# power.net
KiCad netlist of a schematic drawn in Altium Designer
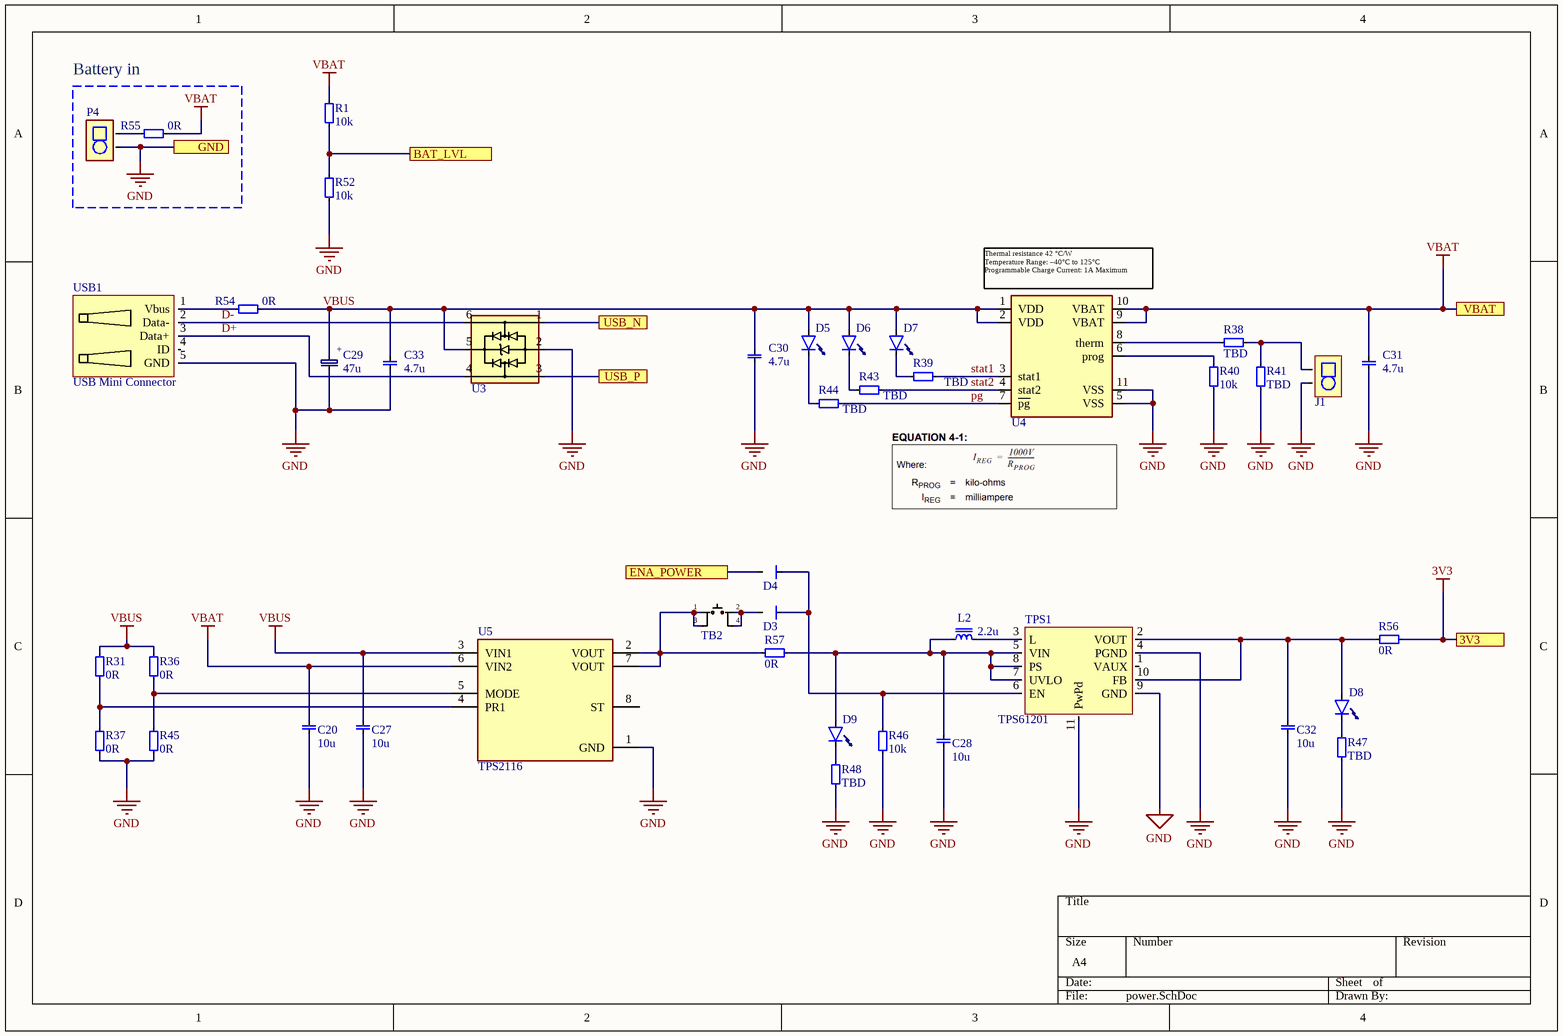
[diagram p0: power.SchDoc]

(export (version "E")
  (design (tool "Eeschema 10.0.6"))
  (components
    (comp (ref "C20")
      (value "10u")
      (footprint "0402 CAP")
      (fields
        (field (name "MANUFACTURER PART NO") "GRM155R61A106ME11D")
        (field (name "Comment") "0402 capacitor")
      )
      (libsource (lib "jclib") (part "0402 capacitor"))
    )
    (comp (ref "C27")
      (value "10u")
      (footprint "0402 CAP")
      (fields
        (field (name "MANUFACTURER PART NO") "GRM155R61A106ME11D")
        (field (name "Comment") "0402 capacitor")
      )
      (libsource (lib "jclib") (part "0402 capacitor"))
    )
    (comp (ref "C28")
      (value "10u")
      (footprint "0402 CAP")
      (fields
        (field (name "MANUFACTURER PART NO") "GRM155R61A106ME11D")
        (field (name "Comment") "0402 capacitor")
      )
      (libsource (lib "jclib") (part "0402 capacitor"))
    )
    (comp (ref "C29")
      (value "47u")
      (footprint "CASE_B")
      (fields (field (name "MANUFACTURER PART NO") "TAJB476M010RNJ") (field (name "Comment") "Cap, case B"))
      (libsource (lib "jclib") (part "Cap, case B"))
    )
    (comp (ref "C30")
      (value "4.7u")
      (footprint "0603 cap")
      (fields
        (field (name "MANUFACTURER PART NO") "GRM188C81C475KE11D")
        (field (name "Comment") "0603, capacitor")
      )
      (libsource (lib "jclib") (part "0603, capacitor"))
    )
    (comp (ref "C31")
      (value "4.7u")
      (footprint "0603 cap")
      (fields
        (field (name "MANUFACTURER PART NO") "GRM188C81C475KE11D")
        (field (name "Comment") "0603, capacitor")
      )
      (libsource (lib "jclib") (part "0603, capacitor"))
    )
    (comp (ref "C32")
      (value "10u")
      (footprint "0402 CAP")
      (fields
        (field (name "MANUFACTURER PART NO") "GRM155R61A106ME11D")
        (field (name "Comment") "0402 capacitor")
      )
      (libsource (lib "jclib") (part "0402 capacitor"))
    )
    (comp (ref "C33")
      (value "4.7u")
      (footprint "0603 cap")
      (fields
        (field (name "MANUFACTURER PART NO") "GRM188C81C475KE11D")
        (field (name "Comment") "0603, capacitor")
      )
      (libsource (lib "jclib") (part "0603, capacitor"))
    )
    (comp (ref "D3")
      (value "Diode, SMD")
      (footprint "SOD323")
      (fields (field (name "MANUFACTURER PART NO") "CUS05S30H3FCT-ND"))
      (libsource (lib "jclib") (part "Diode, SMD"))
    )
    (comp (ref "D4")
      (value "Diode, SMD")
      (footprint "SOD323")
      (fields (field (name "MANUFACTURER PART NO") "CUS05S30H3FCT-ND"))
      (libsource (lib "jclib") (part "Diode, SMD"))
    )
    (comp (ref "D5")
      (value "0603, LED")
      (footprint "0603 LED")
      (fields (field (name "MANUFACTURER PART NO") "5988081107F"))
      (libsource (lib "jclib") (part "0603, LED"))
    )
    (comp (ref "D6")
      (value "0603, LED")
      (footprint "0603 LED")
      (fields (field (name "MANUFACTURER PART NO") "150060SS75003"))
      (libsource (lib "jclib") (part "0603, LED"))
    )
    (comp (ref "D7")
      (value "0603, LED")
      (footprint "0603 LED")
      (fields (field (name "MANUFACTURER PART NO") "150060SS75003"))
      (libsource (lib "jclib") (part "0603, LED"))
    )
    (comp (ref "D8")
      (value "0603, LED")
      (footprint "0603 LED")
      (fields (field (name "MANUFACTURER PART NO") "5988081107F"))
      (libsource (lib "jclib") (part "0603, LED"))
    )
    (comp (ref "D9")
      (value "0603, LED")
      (footprint "0603 LED")
      (fields (field (name "MANUFACTURER PART NO") "5988081107F"))
      (libsource (lib "jclib") (part "0603, LED"))
    )
    (comp (ref "J1")
      (value "Molex 0530480210")
      (footprint "MOLEX_0530480210")
      (description "PicoBlade Header R/A, 1.25 mm,")
      (fields (field (name "MANUFACTURER PART NO") "0530480210"))
      (libsource (lib "jclib") (part "Molex 0530480210"))
    )
    (comp (ref "L2")
      (value "2.2u")
      (footprint "SRR4028")
      (description "2,2µH, 2.0 A, 28 mOhm")
      (fields (field (name "MANUFACTURER PART NO") "SRR4028-2R2Y") (field (name "Comment") "Coil, SRR4028"))
      (libsource (lib "jclib") (part "Coil, SRR4028"))
    )
    (comp (ref "P4")
      (value "JST Connector")
      (footprint "JST_S2B-PH-K-S(LF)(SN)")
      (description "Connector Header Through Hole, Right Angle 2 position")
      (fields (field (name "MANUFACTURER PART NO") "S2B-PH-K-S"))
      (libsource (lib "jclib") (part "JST Connector"))
    )
    (comp (ref "R1")
      (value "10k")
      (footprint "0402 res")
      (description "311-10.0KLRCT-ND")
      (fields (field (name "Comment") "0603, resistor"))
      (libsource (lib "jclib") (part "0603, resistor"))
    )
    (comp (ref "R31")
      (value "0R")
      (footprint "0402 res")
      (fields
        (field (name "MANUFACTURER PART NO") "RMCF0402ZT0R00")
        (field (name "Comment") "0603, resistor")
      )
      (libsource (lib "jclib") (part "0603, resistor"))
    )
    (comp (ref "R36")
      (value "0R")
      (footprint "0402 res")
      (fields
        (field (name "MANUFACTURER PART NO") "RMCF0402ZT0R00")
        (field (name "Comment") "0603, resistor")
      )
      (libsource (lib "jclib") (part "0603, resistor"))
    )
    (comp (ref "R37")
      (value "0R")
      (footprint "0402 res")
      (fields
        (field (name "MANUFACTURER PART NO") "RMCF0402ZT0R00")
        (field (name "Comment") "0603, resistor")
      )
      (libsource (lib "jclib") (part "0603, resistor"))
    )
    (comp (ref "R38")
      (value "TBD")
      (footprint "0402 res")
      (fields (field (name "Comment") "0603, resistor"))
      (libsource (lib "jclib") (part "0603, resistor"))
    )
    (comp (ref "R39")
      (value "TBD")
      (footprint "0402 res")
      (fields (field (name "Comment") "0603, resistor"))
      (libsource (lib "jclib") (part "0603, resistor"))
    )
    (comp (ref "R40")
      (value "10k")
      (footprint "0402 res")
      (fields
        (field (name "MANUFACTURER PART NO") "311-10.0KLRCT-ND")
        (field (name "Comment") "0603, resistor")
      )
      (libsource (lib "jclib") (part "0603, resistor"))
    )
    (comp (ref "R41")
      (value "TBD")
      (footprint "0402 res")
      (fields (field (name "Comment") "0603, resistor"))
      (libsource (lib "jclib") (part "0603, resistor"))
    )
    (comp (ref "R43")
      (value "TBD")
      (footprint "0402 res")
      (fields (field (name "Comment") "0603, resistor"))
      (libsource (lib "jclib") (part "0603, resistor"))
    )
    (comp (ref "R44")
      (value "TBD")
      (footprint "0402 res")
      (fields (field (name "Comment") "0603, resistor"))
      (libsource (lib "jclib") (part "0603, resistor"))
    )
    (comp (ref "R45")
      (value "0R")
      (footprint "0402 res")
      (fields
        (field (name "MANUFACTURER PART NO") "RMCF0402ZT0R00")
        (field (name "Comment") "0603, resistor")
      )
      (libsource (lib "jclib") (part "0603, resistor"))
    )
    (comp (ref "R46")
      (value "10k")
      (footprint "0402 res")
      (fields
        (field (name "MANUFACTURER PART NO") "311-10.0KLRCT-ND")
        (field (name "Comment") "0603, resistor")
      )
      (libsource (lib "jclib") (part "0603, resistor"))
    )
    (comp (ref "R47")
      (value "TBD")
      (footprint "0402 res")
      (fields (field (name "Comment") "0603, resistor"))
      (libsource (lib "jclib") (part "0603, resistor"))
    )
    (comp (ref "R48")
      (value "TBD")
      (footprint "0402 res")
      (fields (field (name "Comment") "0603, resistor"))
      (libsource (lib "jclib") (part "0603, resistor"))
    )
    (comp (ref "R52")
      (value "10k")
      (footprint "0402 res")
      (description "311-10.0KLRCT-ND")
      (fields (field (name "Comment") "0603, resistor"))
      (libsource (lib "jclib") (part "0603, resistor"))
    )
    (comp (ref "R54")
      (value "0R")
      (footprint "0603")
      (fields (field (name "MANUFACTURER PART NO") "541-0.0GCT-ND") (field (name "Comment") "0603, resistor"))
      (libsource (lib "jclib") (part "0603, resistor"))
    )
    (comp (ref "R55")
      (value "0R")
      (footprint "0603")
      (fields (field (name "MANUFACTURER PART NO") "541-0.0GCT-ND") (field (name "Comment") "0603, resistor"))
      (libsource (lib "jclib") (part "0603, resistor"))
    )
    (comp (ref "R56")
      (value "0R")
      (footprint "0603")
      (fields (field (name "MANUFACTURER PART NO") "541-0.0GCT-ND") (field (name "Comment") "0603, resistor"))
      (libsource (lib "jclib") (part "0603, resistor"))
    )
    (comp (ref "R57")
      (value "0R")
      (footprint "0603")
      (fields (field (name "MANUFACTURER PART NO") "541-0.0GCT-ND") (field (name "Comment") "0603, resistor"))
      (libsource (lib "jclib") (part "0603, resistor"))
    )
    (comp (ref "TB2")
      (value "Tactile Button")
      (footprint "tacButton smd")
      (description "Tactile Switch Small Low")
      (fields (field (name "MANUFACTURER PART NO") "430182043816"))
      (libsource (lib "jclib") (part "TacButton SMD"))
    )
    (comp (ref "TPS1")
      (value "TPS61201")
      (footprint "PSON10N")
      (description "TPS6120x Low Input Voltage Synchronous Boost Converter")
      (fields (field (name "MANUFACTURER PART NO") "TPS61201DRCR"))
      (libsource (lib "jclib") (part "TPS6120x"))
    )
    (comp (ref "U3")
      (value "USBLC6-2")
      (footprint "SOT236")
      (description "Very low capacitance 2 data-line and VBUS ESD protection")
      (fields (field (name "MANUFACTURER PART NO") "USBLC6-2SC6"))
      (libsource (lib "jclib") (part "USBLC6-2"))
    )
    (comp (ref "U4")
      (value "MCP73833/4")
      (footprint "DFN10")
      (description "Stand-Alone Linear Li-Ion / Li-Polymer Charge\r\nManagement Controller")
      (fields (field (name "MANUFACTURER PART NO") "MCP73833-NVI/MF"))
      (libsource (lib "jclib") (part "MCP73833/4"))
    )
    (comp (ref "U5")
      (value "TPS2116")
      (footprint "SOTFL50P160X60-8N")
      (description "1.6 V to 5.5 V, 2.5-A Low IQ Power Mux with Manual and Priority Switchover")
      (fields (field (name "MANUFACTURER PART NO") "TPS2116DRLR"))
      (libsource (lib "urad") (part "TPS2116"))
    )
    (comp (ref "USB1")
      (value "USB Mini Connector")
      (footprint "USB Mini TH")
      (fields (field (name "MANUFACTURER PART NO") "XM7D-0512"))
      (libsource (lib "jclib") (part "USB Mini Connector"))
    )
  )
  (nets
    (net (code "1") (name "/BAT_LVL") (class "Default")
      (node (ref "R1") (pin "1") (pinfunction "1_1") (pintype "passive"))
      (node (ref "R52") (pin "0") (pinfunction "0_0") (pintype "passive"))
    )
    (net (code "2") (name "/D+") (class "Default")
      (node (ref "U3") (pin "4") (pinfunction "4_4") (pintype "passive"))
      (node (ref "USB1") (pin "3") (pinfunction "Data+_3") (pintype "passive"))
    )
    (net (code "3") (name "/D-") (class "Default")
      (node (ref "U3") (pin "6") (pinfunction "6_6") (pintype "passive"))
      (node (ref "USB1") (pin "2") (pinfunction "Data-_2") (pintype "passive"))
    )
    (net (code "4") (name "/ENA_POWER") (class "Default")
      (node (ref "D4") (pin "2") (pinfunction "2_2") (pintype "passive"))
    )
    (net (code "5") (name "/USB_N") (class "Default")
      (node (ref "U3") (pin "1") (pinfunction "1_1") (pintype "passive"))
    )
    (net (code "6") (name "/USB_P") (class "Default")
      (node (ref "U3") (pin "3") (pinfunction "3_3") (pintype "passive"))
    )
    (net (code "7") (name "/stat1") (class "Default")
      (node (ref "R39") (pin "1") (pinfunction "1_1") (pintype "passive"))
      (node (ref "U4") (pin "3") (pinfunction "stat1_3") (pintype "passive"))
    )
    (net (code "8") (name "/stat2") (class "Default")
      (node (ref "R43") (pin "1") (pinfunction "1_1") (pintype "passive"))
      (node (ref "U4") (pin "4") (pinfunction "stat2_4") (pintype "passive"))
    )
    (net (code "9") (name "/~{pg}") (class "Default")
      (node (ref "R44") (pin "1") (pinfunction "1_1") (pintype "passive"))
      (node (ref "U4") (pin "7") (pinfunction "~{pg}_7") (pintype "passive"))
    )
    (net (code "10") (name "3V3") (class "Default")
      (node (ref "R56") (pin "0") (pinfunction "0_0") (pintype "passive"))
    )
    (net (code "11") (name "GND") (class "Default")
      (node (ref "C20") (pin "0") (pinfunction "0_0") (pintype "passive"))
      (node (ref "C27") (pin "0") (pinfunction "0_0") (pintype "passive"))
      (node (ref "C28") (pin "0") (pinfunction "0_0") (pintype "passive"))
      (node (ref "C29") (pin "1") (pinfunction "1_1") (pintype "passive"))
      (node (ref "C30") (pin "0") (pinfunction "0_0") (pintype "passive"))
      (node (ref "C31") (pin "0") (pinfunction "0_0") (pintype "passive"))
      (node (ref "C32") (pin "0") (pinfunction "0_0") (pintype "passive"))
      (node (ref "C33") (pin "0") (pinfunction "0_0") (pintype "passive"))
      (node (ref "J1") (pin "2") (pinfunction "2_2") (pintype "passive"))
      (node (ref "P4") (pin "2") (pinfunction "2_2") (pintype "passive"))
      (node (ref "R37") (pin "0") (pinfunction "0_0") (pintype "passive"))
      (node (ref "R40") (pin "0") (pinfunction "0_0") (pintype "passive"))
      (node (ref "R41") (pin "0") (pinfunction "0_0") (pintype "passive"))
      (node (ref "R45") (pin "0") (pinfunction "0_0") (pintype "passive"))
      (node (ref "R46") (pin "0") (pinfunction "0_0") (pintype "passive"))
      (node (ref "R47") (pin "1") (pinfunction "1_1") (pintype "passive"))
      (node (ref "R48") (pin "1") (pinfunction "1_1") (pintype "passive"))
      (node (ref "R52") (pin "1") (pinfunction "1_1") (pintype "passive"))
      (node (ref "TPS1") (pin "11") (pinfunction "PwPd_11") (pintype "passive"))
      (node (ref "TPS1") (pin "4") (pinfunction "PGND_4") (pintype "passive"))
      (node (ref "TPS1") (pin "9") (pinfunction "GND_9") (pintype "passive"))
      (node (ref "U3") (pin "2") (pinfunction "2_2") (pintype "passive"))
      (node (ref "U4") (pin "11") (pinfunction "VSS_11") (pintype "passive"))
      (node (ref "U4") (pin "5") (pinfunction "VSS_5") (pintype "passive"))
      (node (ref "U5") (pin "1") (pinfunction "GND_1") (pintype "passive"))
      (node (ref "USB1") (pin "5") (pinfunction "GND_5") (pintype "passive"))
    )
    (net (code "12") (name "Net-(D3-Pad2)") (class "Default")
      (node (ref "D3") (pin "2") (pinfunction "2_2") (pintype "passive"))
      (node (ref "TB2") (pin "2") (pinfunction "2_2") (pintype "passive"))
      (node (ref "TB2") (pin "4") (pinfunction "4_4") (pintype "passive"))
    )
    (net (code "13") (name "Net-(D5-Cathode)") (class "Default")
      (node (ref "D5") (pin "0") (pinfunction "Cathode_0") (pintype "passive"))
      (node (ref "R44") (pin "0") (pinfunction "0_0") (pintype "passive"))
    )
    (net (code "14") (name "Net-(D6-Cathode)") (class "Default")
      (node (ref "D6") (pin "0") (pinfunction "Cathode_0") (pintype "passive"))
      (node (ref "R43") (pin "0") (pinfunction "0_0") (pintype "passive"))
    )
    (net (code "15") (name "Net-(D7-Cathode)") (class "Default")
      (node (ref "D7") (pin "0") (pinfunction "Cathode_0") (pintype "passive"))
      (node (ref "R39") (pin "0") (pinfunction "0_0") (pintype "passive"))
    )
    (net (code "16") (name "Net-(D8-Cathode)") (class "Default")
      (node (ref "D8") (pin "0") (pinfunction "Cathode_0") (pintype "passive"))
      (node (ref "R47") (pin "0") (pinfunction "0_0") (pintype "passive"))
    )
    (net (code "17") (name "Net-(D9-Cathode)") (class "Default")
      (node (ref "D9") (pin "0") (pinfunction "Cathode_0") (pintype "passive"))
      (node (ref "R48") (pin "0") (pinfunction "0_0") (pintype "passive"))
    )
    (net (code "18") (name "Net-(J1-Pad1)") (class "Default")
      (node (ref "J1") (pin "1") (pinfunction "1_1") (pintype "passive"))
      (node (ref "R38") (pin "0") (pinfunction "0_0") (pintype "passive"))
      (node (ref "R41") (pin "1") (pinfunction "1_1") (pintype "passive"))
    )
    (net (code "19") (name "Net-(P4-Pad1)") (class "Default")
      (node (ref "P4") (pin "1") (pinfunction "1_1") (pintype "passive"))
      (node (ref "R55") (pin "1") (pinfunction "1_1") (pintype "passive"))
    )
    (net (code "20") (name "Net-(R57-Pad1)") (class "Default")
      (node (ref "R57") (pin "1") (pinfunction "1_1") (pintype "passive"))
      (node (ref "TB2") (pin "1") (pinfunction "1_1") (pintype "passive"))
      (node (ref "TB2") (pin "3") (pinfunction "3_3") (pintype "passive"))
      (node (ref "U5") (pin "2") (pinfunction "VOUT_2") (pintype "passive"))
      (node (ref "U5") (pin "7") (pinfunction "VOUT_7") (pintype "passive"))
    )
    (net (code "21") (name "Net-(TPS1-EN)") (class "Default")
      (node (ref "D3") (pin "1") (pinfunction "1_1") (pintype "passive"))
      (node (ref "D4") (pin "1") (pinfunction "1_1") (pintype "passive"))
      (node (ref "R46") (pin "1") (pinfunction "1_1") (pintype "passive"))
      (node (ref "TPS1") (pin "6") (pinfunction "EN_6") (pintype "passive"))
    )
    (net (code "22") (name "Net-(TPS1-FB)") (class "Default")
      (node (ref "C32") (pin "1") (pinfunction "1_1") (pintype "passive"))
      (node (ref "D8") (pin "1") (pinfunction "1_1") (pintype "passive"))
      (node (ref "R56") (pin "1") (pinfunction "1_1") (pintype "passive"))
      (node (ref "TPS1") (pin "10") (pinfunction "FB_10") (pintype "passive"))
      (node (ref "TPS1") (pin "2") (pinfunction "VOUT_2") (pintype "passive"))
    )
    (net (code "23") (name "Net-(TPS1-L)") (class "Default")
      (node (ref "L2") (pin "1") (pinfunction "1_1") (pintype "passive"))
      (node (ref "TPS1") (pin "3") (pinfunction "L_3") (pintype "passive"))
    )
    (net (code "24") (name "Net-(TPS1-PS)") (class "Default")
      (node (ref "C28") (pin "1") (pinfunction "1_1") (pintype "passive"))
      (node (ref "D9") (pin "1") (pinfunction "1_1") (pintype "passive"))
      (node (ref "L2") (pin "2") (pinfunction "2_2") (pintype "passive"))
      (node (ref "R57") (pin "0") (pinfunction "0_0") (pintype "passive"))
      (node (ref "TPS1") (pin "5") (pinfunction "VIN_5") (pintype "passive"))
      (node (ref "TPS1") (pin "7") (pinfunction "UVLO_7") (pintype "passive"))
      (node (ref "TPS1") (pin "8") (pinfunction "PS_8") (pintype "passive"))
    )
    (net (code "25") (name "Net-(U4-prog)") (class "Default")
      (node (ref "R40") (pin "1") (pinfunction "1_1") (pintype "passive"))
      (node (ref "U4") (pin "6") (pinfunction "prog_6") (pintype "passive"))
    )
    (net (code "26") (name "Net-(U4-therm)") (class "Default")
      (node (ref "R38") (pin "1") (pinfunction "1_1") (pintype "passive"))
      (node (ref "U4") (pin "8") (pinfunction "therm_8") (pintype "passive"))
    )
    (net (code "27") (name "Net-(U5-MODE)") (class "Default")
      (node (ref "R36") (pin "0") (pinfunction "0_0") (pintype "passive"))
      (node (ref "R45") (pin "1") (pinfunction "1_1") (pintype "passive"))
      (node (ref "U5") (pin "5") (pinfunction "MODE_5") (pintype "passive"))
    )
    (net (code "28") (name "Net-(U5-PR1)") (class "Default")
      (node (ref "R31") (pin "0") (pinfunction "0_0") (pintype "passive"))
      (node (ref "R37") (pin "1") (pinfunction "1_1") (pintype "passive"))
      (node (ref "U5") (pin "4") (pinfunction "PR1_4") (pintype "passive"))
    )
    (net (code "29") (name "Net-(USB1-Vbus)") (class "Default")
      (node (ref "R54") (pin "1") (pinfunction "1_1") (pintype "passive"))
      (node (ref "USB1") (pin "1") (pinfunction "Vbus_1") (pintype "passive"))
    )
    (net (code "30") (name "VBAT") (class "Default")
      (node (ref "C20") (pin "1") (pinfunction "1_1") (pintype "passive"))
      (node (ref "C31") (pin "1") (pinfunction "1_1") (pintype "passive"))
      (node (ref "R1") (pin "0") (pinfunction "0_0") (pintype "passive"))
      (node (ref "R55") (pin "0") (pinfunction "0_0") (pintype "passive"))
      (node (ref "U4") (pin "10") (pinfunction "VBAT_10") (pintype "passive"))
      (node (ref "U4") (pin "9") (pinfunction "VBAT_9") (pintype "passive"))
      (node (ref "U5") (pin "6") (pinfunction "VIN2_6") (pintype "passive"))
    )
    (net (code "31") (name "VBUS") (class "Default")
      (node (ref "C27") (pin "1") (pinfunction "1_1") (pintype "passive"))
      (node (ref "C29") (pin "2") (pinfunction "2_2") (pintype "passive"))
      (node (ref "C30") (pin "1") (pinfunction "1_1") (pintype "passive"))
      (node (ref "C33") (pin "1") (pinfunction "1_1") (pintype "passive"))
      (node (ref "D5") (pin "1") (pinfunction "1_1") (pintype "passive"))
      (node (ref "D6") (pin "1") (pinfunction "1_1") (pintype "passive"))
      (node (ref "D7") (pin "1") (pinfunction "1_1") (pintype "passive"))
      (node (ref "R31") (pin "1") (pinfunction "1_1") (pintype "passive"))
      (node (ref "R36") (pin "1") (pinfunction "1_1") (pintype "passive"))
      (node (ref "R54") (pin "0") (pinfunction "0_0") (pintype "passive"))
      (node (ref "U3") (pin "5") (pinfunction "5_5") (pintype "passive"))
      (node (ref "U4") (pin "1") (pinfunction "VDD_1") (pintype "passive"))
      (node (ref "U4") (pin "2") (pinfunction "VDD_2") (pintype "passive"))
      (node (ref "U5") (pin "3") (pinfunction "VIN1_3") (pintype "passive"))
    )
    (net (code "32") (name "unconnected-(TPS1-VAUX-Pad1)") (class "Default")
      (node (ref "TPS1") (pin "1") (pinfunction "VAUX_1") (pintype "passive"))
    )
    (net (code "33") (name "unconnected-(U5-ST-Pad8)") (class "Default")
      (node (ref "U5") (pin "8") (pinfunction "ST_8") (pintype "passive"))
    )
    (net (code "34") (name "unconnected-(USB1-ID-Pad4)") (class "Default")
      (node (ref "USB1") (pin "4") (pinfunction "ID_4") (pintype "passive"))
    )
  )
)
